# 51-2001-01-11_04_Power_Module_Schematic.net
KiCad netlist of a schematic drawn in Altium Designer
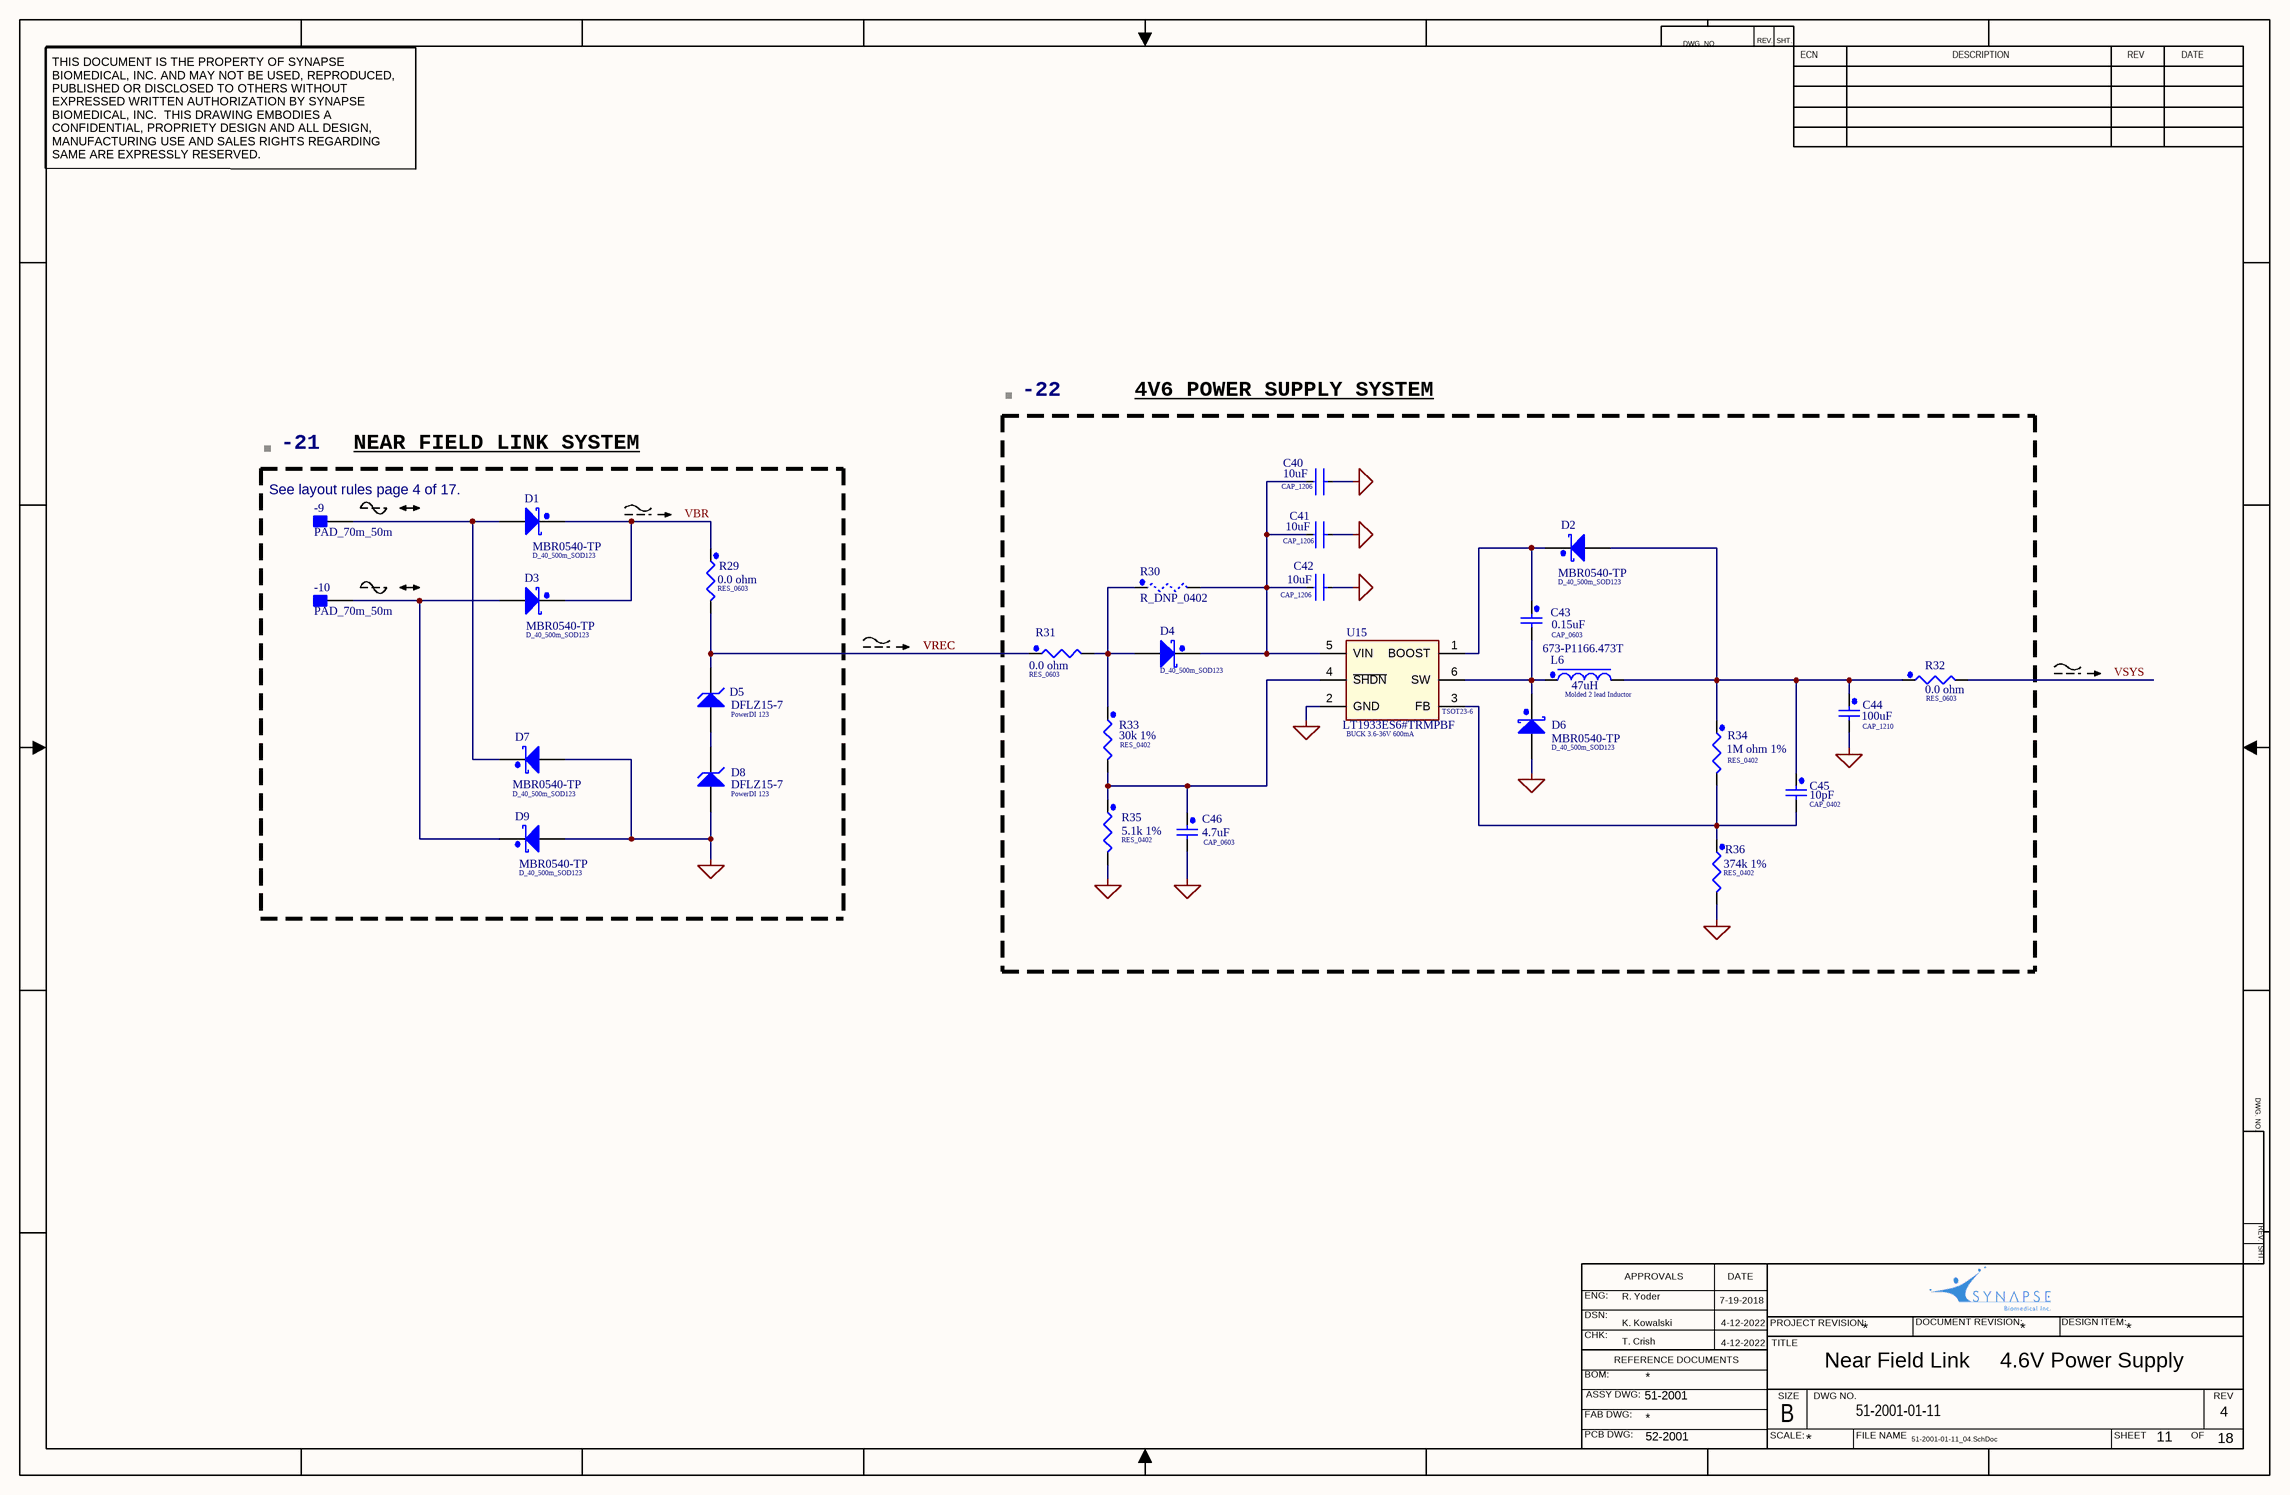
[diagram p0: 51-2001-01-11_04 Power Module Schematic.SchDoc]

(export (version "E")
  (design (tool "Eeschema 10.0.6"))
  (components
    (comp (ref "-9")
      (value "PAD_70m_50m")
      (footprint "PAD_70m_50m")
      (description "SMT pad rectangular")
      (libsource (lib "NNPS Integrated Parts") (part "PAD_70m_50m"))
    )
    (comp (ref "-10")
      (value "PAD_70m_50m")
      (footprint "PAD_70m_50m")
      (description "SMT pad rectangular")
      (libsource (lib "NNPS Integrated Parts") (part "PAD_70m_50m"))
    )
    (comp (ref "-21")
      (value "BOM_S1")
      (description "BOM item small graphic")
      (fields (field (name "XDESCRIPTION") "NEAR FIELD LINK SYSTEM"))
      (libsource (lib "BOM_sym") (part "BOM_S1"))
    )
    (comp (ref "-22")
      (value "BOM_S1")
      (description "BOM item small graphic")
      (fields (field (name "XDESCRIPTION") "4V6 POWER SUPPLY SYSTEM"))
      (libsource (lib "BOM_sym") (part "BOM_S1"))
    )
    (comp (ref "C40")
      (value "10uF")
      (footprint "FP-GRT31C-0_2-IPC_A")
      (description "Multi-Layer Ceramic Capacitor 10uF 50V X5R ±10% 1206 Emboss T/R\r\nGRT31CR61H106KE01L")
      (fields (field (name "TOLERANCE") "10%") (field (name "CASE/PACKAGE") "CAP_1206"))
      (libsource (lib "Altium Content Vault") (part "02cd4be3c70576c341d710602a673aa"))
    )
    (comp (ref "C41")
      (value "10uF")
      (footprint "FP-GRT31C-0_2-IPC_A")
      (description "Multi-Layer Ceramic Capacitor 10uF 50V X5R ±10% 1206 Emboss T/R\r\nGRT31CR61H106KE01L")
      (fields (field (name "TOLERANCE") "10%") (field (name "CASE/PACKAGE") "CAP_1206"))
      (libsource (lib "Altium Content Vault") (part "02cd4be3c70576c341d710602a673aa"))
    )
    (comp (ref "C42")
      (value "10uF")
      (footprint "FP-GRT31C-0_2-IPC_A")
      (description "Multi-Layer Ceramic Capacitor 10uF 50V X5R ±10% 1206 Emboss T/R\r\nGRT31CR61H106KE01L")
      (fields (field (name "TOLERANCE") "10%") (field (name "CASE/PACKAGE") "CAP_1206"))
      (libsource (lib "Altium Content Vault") (part "02cd4be3c70576c341d710602a673aa"))
    )
    (comp (ref "C43")
      (value "0.15uF")
      (footprint "CAP_0603")
      (description "0.15uF, 16V, X7R, 10%, 0603, RoHS")
      (fields
        (field (name "MFR") "Murata Electronics North America")
        (field (name "PACKAGEDESCRIPTION") "CAP_0603")
        (field (name "MPN") "GRM188R71C154KA01D")
      )
      (libsource (lib "NNPS Integrated Parts") (part "GRM188R71C154KA01D"))
    )
    (comp (ref "C44")
      (value "100uF")
      (footprint "CAP_1210")
      (description "100uF, 10V, X5R, 20%, 1210, RoHS")
      (fields
        (field (name "MFR") "Murata Electronics North America")
        (field (name "PACKAGEDESCRIPTION") "CAP_1210")
        (field (name "MPN") "GRM32ER61A107ME20L")
      )
      (libsource (lib "NNPS Integrated Parts") (part "LMK325BJ107MM-T"))
    )
    (comp (ref "C45")
      (value "10pF")
      (footprint "CAP_0402")
      (description "10pF, 50V, C0G, 5%, 0402, RoHS")
      (fields
        (field (name "MFR") "Murata Electronics North America")
        (field (name "PACKAGEDESCRIPTION") "CAP_0402")
        (field (name "MPN") "GRM1555C1H100JA01D")
      )
      (libsource (lib "NNPS Integrated Parts") (part "GRM1555C1H100JZ01"))
    )
    (comp (ref "C46")
      (value "4.7uF")
      (footprint "CAP_0603")
      (description "4.7uF, 10V, X5R, 10%, 0603, RoHS")
      (fields
        (field (name "MFR") "Murata Electronics North America")
        (field (name "PACKAGEDESCRIPTION") "CAP_0603")
        (field (name "MPN") "GRM185R61A475KE11D")
      )
      (libsource (lib "NNPS Integrated Parts") (part "LMK107BJ475KA-T"))
    )
    (comp (ref "D1")
      (value "D_40_500m_SOD123")
      (footprint "SOD123")
      (description "Schotty Diode, 40V, 500mA, SOD123, RoHS")
      (fields (field (name "MFR") "Micro Commercial Co.") (field (name "MPN") "MBR0540-TP"))
      (libsource (lib "NNPS Integrated Parts") (part "MBR0540-TP"))
    )
    (comp (ref "D2")
      (value "D_40_500m_SOD123")
      (footprint "SOD123")
      (description "Schotty Diode, 40V, 500mA, SOD123, RoHS")
      (fields (field (name "MFR") "Micro Commercial Co.") (field (name "MPN") "MBR0540-TP"))
      (libsource (lib "NNPS Integrated Parts") (part "MBR0540-TP"))
    )
    (comp (ref "D3")
      (value "D_40_500m_SOD123")
      (footprint "SOD123")
      (description "Schotty Diode, 40V, 500mA, SOD123, RoHS")
      (fields (field (name "MFR") "Micro Commercial Co.") (field (name "MPN") "MBR0540-TP"))
      (libsource (lib "NNPS Integrated Parts") (part "MBR0540-TP"))
    )
    (comp (ref "D4")
      (value "D_40_500m_SOD123")
      (footprint "SOD123")
      (description "Schotty Diode, 40V, 500mA, SOD123, RoHS")
      (fields (field (name "MFR") "Micro Commercial Co.") (field (name "MPN") "MBR0540-TP"))
      (libsource (lib "NNPS Integrated Parts") (part "MBR0540-TP"))
    )
    (comp (ref "D5")
      (value "Zener Diode, 15V, 1W, DI123, RoHS")
      (footprint "POWERDI")
      (fields
        (field (name "MFR") "Diodes Inc.")
        (field (name "PACKAGEDESCRIPTION") "PowerDI 123")
        (field (name "MPN") "DFLZ15-7")
      )
      (libsource (lib "NNPS Integrated Parts") (part "DFLZ15-7"))
    )
    (comp (ref "D6")
      (value "D_40_500m_SOD123")
      (footprint "SOD123")
      (description "Schotty Diode, 40V, 500mA, SOD123, RoHS")
      (fields (field (name "MFR") "Micro Commercial Co.") (field (name "MPN") "MBR0540-TP"))
      (libsource (lib "NNPS Integrated Parts") (part "MBR0540-TP"))
    )
    (comp (ref "D7")
      (value "D_40_500m_SOD123")
      (footprint "SOD123")
      (description "Schotty Diode, 40V, 500mA, SOD123, RoHS")
      (fields (field (name "MFR") "Micro Commercial Co.") (field (name "MPN") "MBR0540-TP"))
      (libsource (lib "NNPS Integrated Parts") (part "MBR0540-TP"))
    )
    (comp (ref "D8")
      (value "Zener Diode, 15V, 1W, DI123, RoHS")
      (footprint "POWERDI")
      (fields
        (field (name "MFR") "Diodes Inc.")
        (field (name "PACKAGEDESCRIPTION") "PowerDI 123")
        (field (name "MPN") "DFLZ15-7")
      )
      (libsource (lib "NNPS Integrated Parts") (part "DFLZ15-7"))
    )
    (comp (ref "D9")
      (value "D_40_500m_SOD123")
      (footprint "SOD123")
      (description "Schotty Diode, 40V, 500mA, SOD123, RoHS")
      (fields (field (name "MFR") "Micro Commercial Co.") (field (name "MPN") "MBR0540-TP"))
      (libsource (lib "NNPS Integrated Parts") (part "MBR0540-TP"))
    )
    (comp (ref "L6")
      (value "47uH")
      (footprint "IND-P1166NL")
      (description "47uH, 830mA, 20%, RoHS")
      (fields
        (field (name "MFR") "Pulse")
        (field (name "PACKAGEDESCRIPTION") "Molded 2 lead Inductor")
        (field (name "SUPPLIER PART NUMBER 1") "673-P1166.473T")
        (field (name "MPN") "P1166.473NLT")
      )
      (libsource (lib "NNPS Integrated Parts") (part "P1166.473T"))
    )
    (comp (ref "R29")
      (value "0.0 ohm")
      (footprint "RES_0603")
      (description "0.0 ohm, 1/16W, 0603, RoHS")
      (fields
        (field (name "MFR") "Vishay Dale")
        (field (name "PACKAGEDESCRIPTION") "RES_0603")
        (field (name "MPN") "CRCW06030000Z0EA")
      )
      (libsource (lib "NNPS Integrated Parts") (part "MCR03ERTJ000"))
    )
    (comp (ref "R30")
      (value "R_DNP_0402")
      (footprint "RES_0402")
      (description "DO NOT POPULATE")
      (libsource (lib "NNPS Integrated Parts") (part "R_DNP_0402"))
    )
    (comp (ref "R31")
      (value "0.0 ohm")
      (footprint "RES_0603")
      (description "0.0 ohm, 1/16W, 0603, RoHS")
      (fields
        (field (name "MFR") "Vishay Dale")
        (field (name "PACKAGEDESCRIPTION") "RES_0603")
        (field (name "MPN") "CRCW06030000Z0EA")
      )
      (libsource (lib "NNPS Integrated Parts") (part "MCR03ERTJ000"))
    )
    (comp (ref "R32")
      (value "0.0 ohm")
      (footprint "RES_0603")
      (description "0.0 ohm, 1/16W, 0603, RoHS")
      (fields
        (field (name "MFR") "Vishay Dale")
        (field (name "PACKAGEDESCRIPTION") "RES_0603")
        (field (name "MPN") "CRCW06030000Z0EA")
      )
      (libsource (lib "NNPS Integrated Parts") (part "MCR03ERTJ000"))
    )
    (comp (ref "R33")
      (value "30k 1%")
      (footprint "RES_0402")
      (description "30k ohm, 1%, 1/16W, 0402, RoHS")
      (fields
        (field (name "MFR") "Vishay Dale")
        (field (name "PACKAGEDESCRIPTION") "RES_0402")
        (field (name "MPN") "CRCW040230K0FKED")
      )
      (libsource (lib "NNPS Integrated Parts") (part "MCR01MZPF3002"))
    )
    (comp (ref "R34")
      (value "1M ohm 1%")
      (footprint "RES_0402")
      (description "1M ohm, 1/16W, 1%, 0402, RoHS")
      (fields
        (field (name "MFR") "Vishay Dale")
        (field (name "PACKAGEDESCRIPTION") "RES_0402")
        (field (name "MPN") "CRCW04021M00FKED")
      )
      (libsource (lib "NNPS Integrated Parts") (part "MCR01MZPF1004"))
    )
    (comp (ref "R35")
      (value "5.1k 1%")
      (footprint "RES_0402")
      (description "5.1K ohm, 1%, 1/16W, smd, 0402, RoHS")
      (fields
        (field (name "MFR") "Vishay Dale")
        (field (name "PACKAGEDESCRIPTION") "RES_0402")
        (field (name "MPN") "CRCW04025K10FKED")
      )
      (libsource (lib "NNPS Integrated Parts") (part "MCR01MZPF5101"))
    )
    (comp (ref "R36")
      (value "374k 1%")
      (footprint "RES_0402")
      (description "374k ohm, 1%, 1/16W, 0402,RoHS")
      (fields
        (field (name "MFR") "Vishay Dale")
        (field (name "PACKAGEDESCRIPTION") "RES_0402")
        (field (name "MPN") "CRCW0402374KFKED")
      )
      (libsource (lib "NNPS Integrated Parts") (part "CRCW0402374KFKED"))
    )
    (comp (ref "U15")
      (value "BUCK 3.6-36V 600mA")
      (footprint "SOT23-6")
      (description "DC buck, 3.6-36V, 600mA, TSOT23-6, RoHS")
      (fields
        (field (name "MFR") "Linear Technology")
        (field (name "PACKAGEDESCRIPTION") "TSOT23-6")
        (field (name "MPN") "LT1933ES6#TRMPBF")
      )
      (libsource (lib "NNPS Integrated Parts") (part "LT1933ES6"))
    )
  )
  (nets
    (net (code "1") (name "/VBR") (class "Default")
      (node (ref "D1") (pin "1") (pinfunction "C_1") (pintype "passive"))
      (node (ref "D3") (pin "1") (pinfunction "C_1") (pintype "passive"))
      (node (ref "R29") (pin "1") (pinfunction "1_1") (pintype "passive"))
    )
    (net (code "2") (name "/VREC") (class "Default")
      (node (ref "D5") (pin "1") (pinfunction "C_1") (pintype "passive"))
      (node (ref "R29") (pin "2") (pinfunction "2_2") (pintype "passive"))
      (node (ref "R31") (pin "1") (pinfunction "1_1") (pintype "passive"))
    )
    (net (code "3") (name "/VSYS") (class "Default")
      (node (ref "R32") (pin "2") (pinfunction "2_2") (pintype "passive"))
    )
    (net (code "4") (name "GND") (class "Default")
      (node (ref "C40") (pin "1") (pinfunction "1_1") (pintype "passive"))
      (node (ref "C41") (pin "1") (pinfunction "1_1") (pintype "passive"))
      (node (ref "C42") (pin "1") (pinfunction "1_1") (pintype "passive"))
      (node (ref "C44") (pin "2") (pinfunction "2_2") (pintype "passive"))
      (node (ref "C46") (pin "2") (pinfunction "2_2") (pintype "passive"))
      (node (ref "D6") (pin "2") (pinfunction "A_2") (pintype "passive"))
      (node (ref "D7") (pin "2") (pinfunction "A_2") (pintype "passive"))
      (node (ref "D8") (pin "2") (pinfunction "A_2") (pintype "passive"))
      (node (ref "D9") (pin "2") (pinfunction "A_2") (pintype "passive"))
      (node (ref "R35") (pin "2") (pinfunction "2_2") (pintype "passive"))
      (node (ref "R36") (pin "2") (pinfunction "2_2") (pintype "passive"))
      (node (ref "U15") (pin "2") (pinfunction "GND_2") (pintype "passive"))
    )
    (net (code "5") (name "Net-(D1-A)") (class "Default")
      (node (ref "-9") (pin "1") (pinfunction "1_1") (pintype "passive"))
      (node (ref "D1") (pin "2") (pinfunction "A_2") (pintype "passive"))
      (node (ref "D7") (pin "1") (pinfunction "C_1") (pintype "passive"))
    )
    (net (code "6") (name "Net-(D2-A)") (class "Default")
      (node (ref "C44") (pin "1") (pinfunction "1_1") (pintype "passive"))
      (node (ref "C45") (pin "1") (pinfunction "1_1") (pintype "passive"))
      (node (ref "D2") (pin "2") (pinfunction "A_2") (pintype "passive"))
      (node (ref "L6") (pin "2") (pinfunction "2_2") (pintype "passive"))
      (node (ref "R32") (pin "1") (pinfunction "1_1") (pintype "passive"))
      (node (ref "R34") (pin "1") (pinfunction "1_1") (pintype "passive"))
    )
    (net (code "7") (name "Net-(D2-C)") (class "Default")
      (node (ref "C43") (pin "1") (pinfunction "1_1") (pintype "passive"))
      (node (ref "D2") (pin "1") (pinfunction "C_1") (pintype "passive"))
      (node (ref "U15") (pin "1") (pinfunction "BOOST_1") (pintype "passive"))
    )
    (net (code "8") (name "Net-(D3-A)") (class "Default")
      (node (ref "-10") (pin "1") (pinfunction "1_1") (pintype "passive"))
      (node (ref "D3") (pin "2") (pinfunction "A_2") (pintype "passive"))
      (node (ref "D9") (pin "1") (pinfunction "C_1") (pintype "passive"))
    )
    (net (code "9") (name "Net-(D4-A)") (class "Default")
      (node (ref "D4") (pin "2") (pinfunction "A_2") (pintype "passive"))
      (node (ref "R30") (pin "1") (pinfunction "1_1") (pintype "passive"))
      (node (ref "R31") (pin "2") (pinfunction "2_2") (pintype "passive"))
      (node (ref "R33") (pin "1") (pinfunction "1_1") (pintype "passive"))
    )
    (net (code "10") (name "Net-(D4-C)") (class "Default")
      (node (ref "C40") (pin "2") (pinfunction "2_2") (pintype "passive"))
      (node (ref "C41") (pin "2") (pinfunction "2_2") (pintype "passive"))
      (node (ref "C42") (pin "2") (pinfunction "2_2") (pintype "passive"))
      (node (ref "D4") (pin "1") (pinfunction "C_1") (pintype "passive"))
      (node (ref "R30") (pin "2") (pinfunction "2_2") (pintype "passive"))
      (node (ref "U15") (pin "5") (pinfunction "VIN_5") (pintype "passive"))
    )
    (net (code "11") (name "Net-(D5-A)") (class "Default")
      (node (ref "D5") (pin "2") (pinfunction "A_2") (pintype "passive"))
      (node (ref "D8") (pin "1") (pinfunction "C_1") (pintype "passive"))
    )
    (net (code "12") (name "Net-(D6-C)") (class "Default")
      (node (ref "C43") (pin "2") (pinfunction "2_2") (pintype "passive"))
      (node (ref "D6") (pin "1") (pinfunction "C_1") (pintype "passive"))
      (node (ref "L6") (pin "1") (pinfunction "1_1") (pintype "passive"))
      (node (ref "U15") (pin "6") (pinfunction "SW_6") (pintype "passive"))
    )
    (net (code "13") (name "Net-(U15-FB)") (class "Default")
      (node (ref "C45") (pin "2") (pinfunction "2_2") (pintype "passive"))
      (node (ref "R34") (pin "2") (pinfunction "2_2") (pintype "passive"))
      (node (ref "R36") (pin "1") (pinfunction "1_1") (pintype "passive"))
      (node (ref "U15") (pin "3") (pinfunction "FB_3") (pintype "passive"))
    )
    (net (code "14") (name "Net-(U15-SHDN)") (class "Default")
      (node (ref "C46") (pin "1") (pinfunction "1_1") (pintype "passive"))
      (node (ref "R33") (pin "2") (pinfunction "2_2") (pintype "passive"))
      (node (ref "R35") (pin "1") (pinfunction "1_1") (pintype "passive"))
      (node (ref "U15") (pin "4") (pinfunction "SHDN_4") (pintype "passive"))
    )
  )
)
